# STM32H7.net
KiCad netlist of a schematic drawn in Altium Designer
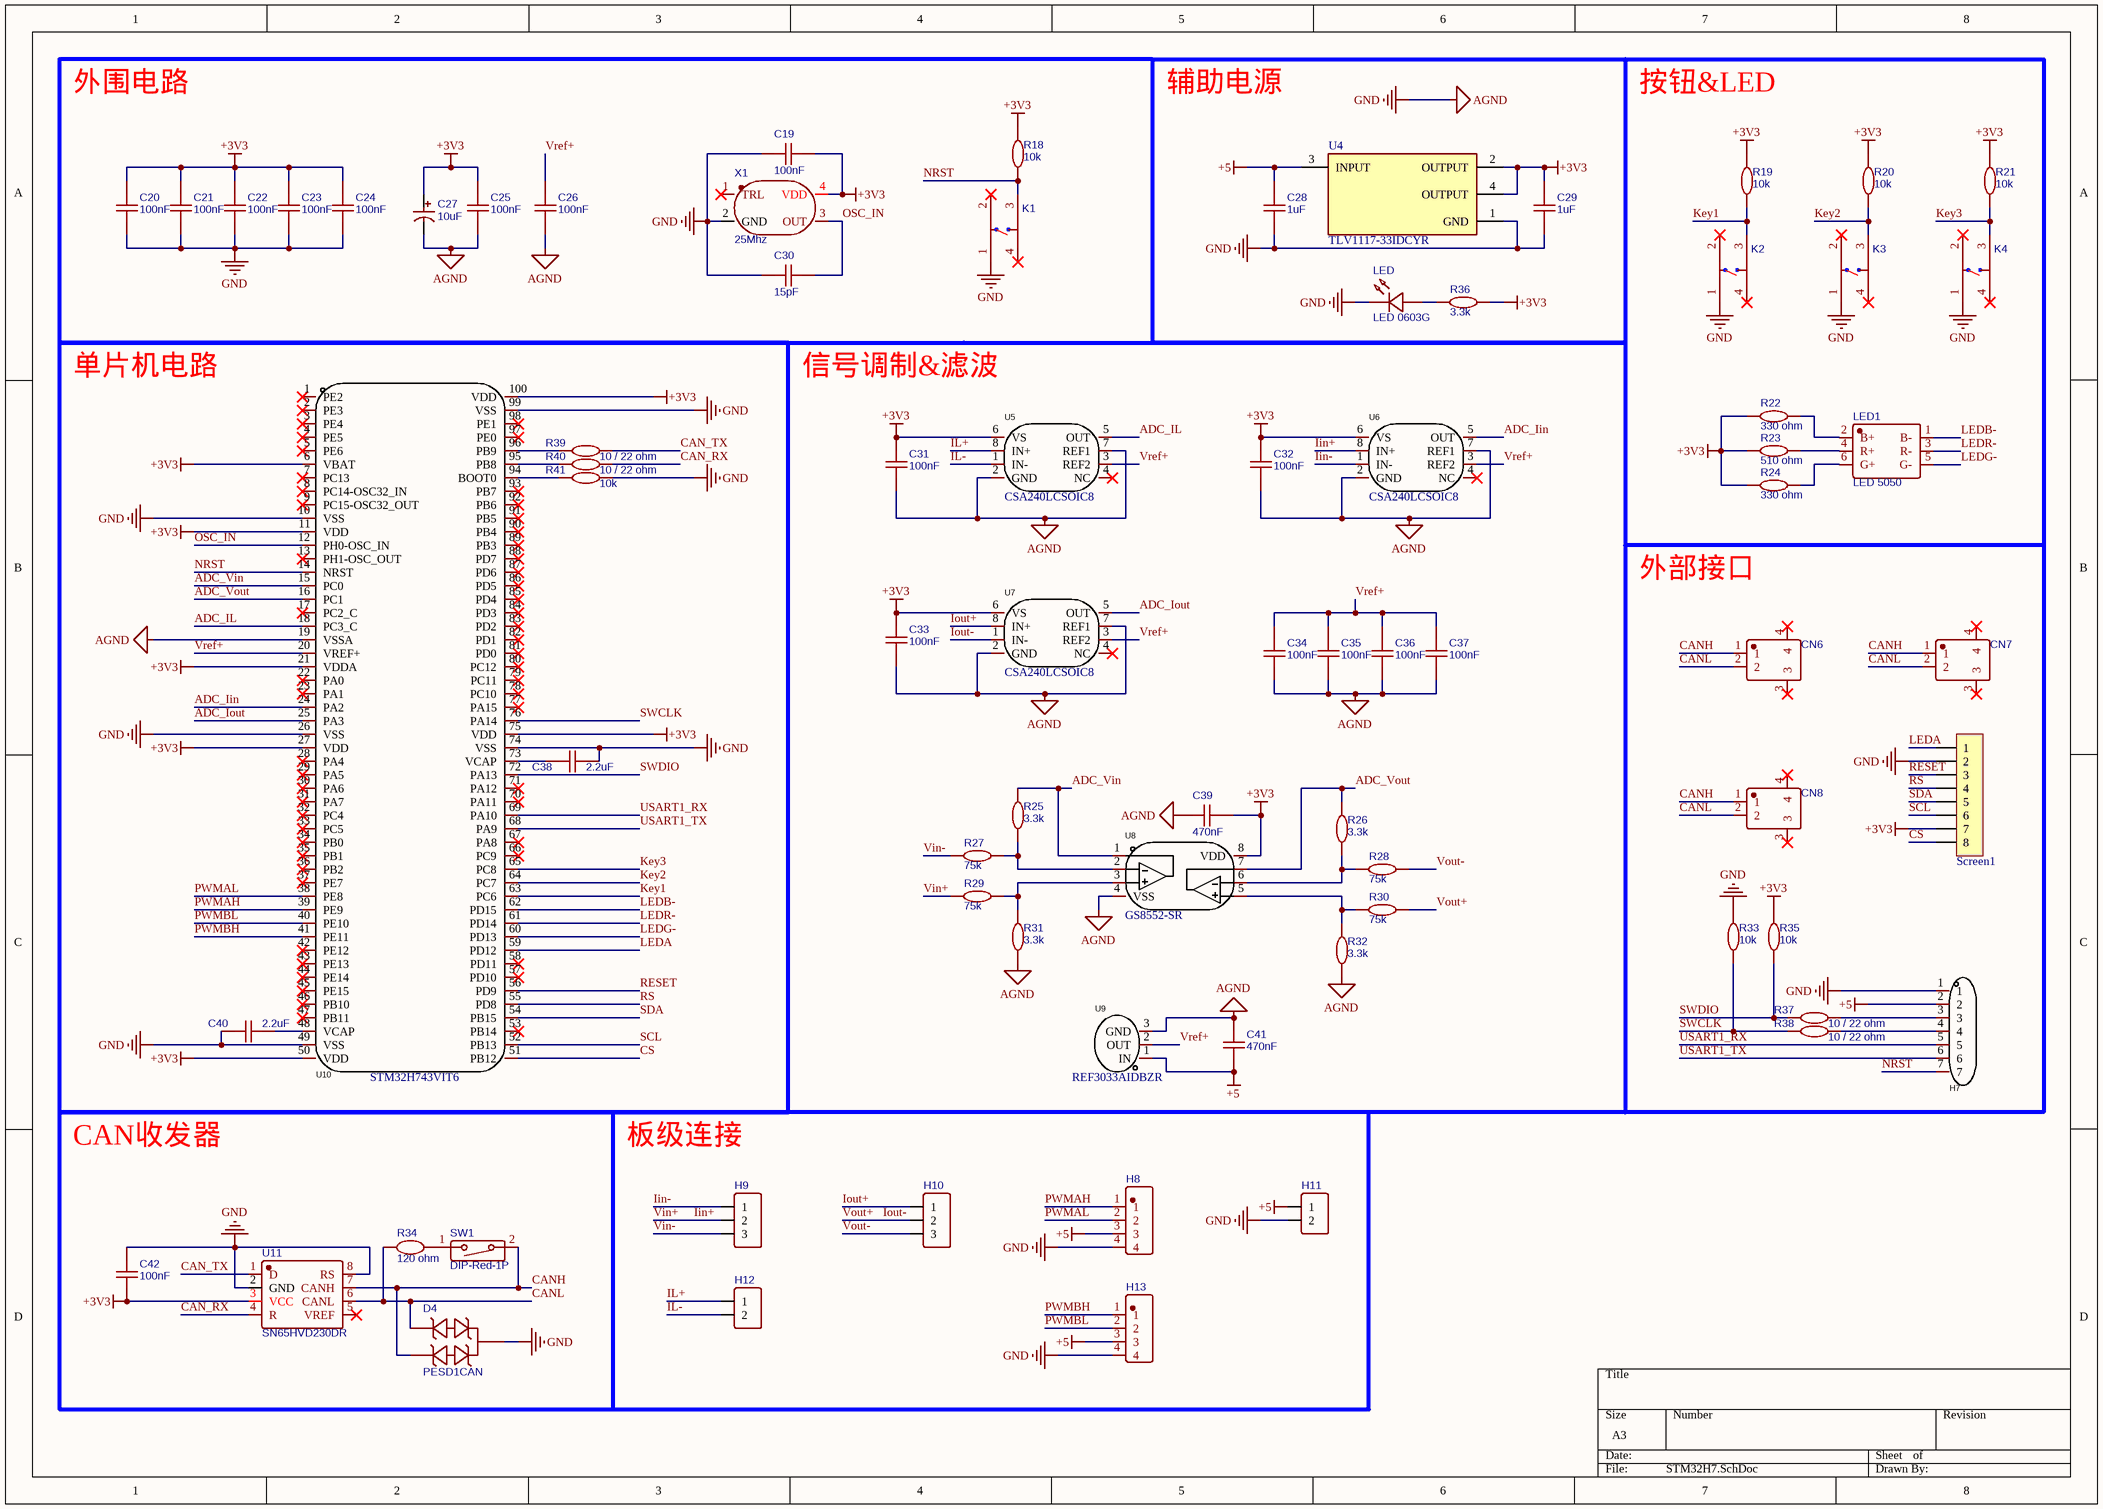
[diagram p0: STM32H7.SchDoc]

(export (version "E")
  (design (tool "Eeschema 10.0.6"))
  (components
    (comp (ref "C19")
      (value "100nF")
      (footprint "C0603")
      (fields
        (field (name "BOM_MANUFACTURER PART") "CC0603KRX7R9BB104")
        (field (name "BOM_SUPPLIER PART") "C14663")
      )
      (libsource (lib "RC_schlib") (part "C0603"))
    )
    (comp (ref "C20")
      (value "100nF")
      (footprint "C0603")
      (fields
        (field (name "BOM_MANUFACTURER PART") "CC0603KRX7R9BB104")
        (field (name "BOM_SUPPLIER PART") "C14663")
      )
      (libsource (lib "RC_schlib") (part "C0603"))
    )
    (comp (ref "C21")
      (value "100nF")
      (footprint "C0603")
      (fields
        (field (name "BOM_MANUFACTURER PART") "CC0603KRX7R9BB104")
        (field (name "BOM_SUPPLIER PART") "C14663")
      )
      (libsource (lib "RC_schlib") (part "C0603"))
    )
    (comp (ref "C22")
      (value "100nF")
      (footprint "C0603")
      (fields
        (field (name "BOM_MANUFACTURER PART") "CC0603KRX7R9BB104")
        (field (name "BOM_SUPPLIER PART") "C14663")
      )
      (libsource (lib "RC_schlib") (part "C0603"))
    )
    (comp (ref "C23")
      (value "100nF")
      (footprint "C0603")
      (fields
        (field (name "BOM_MANUFACTURER PART") "CC0603KRX7R9BB104")
        (field (name "BOM_SUPPLIER PART") "C14663")
      )
      (libsource (lib "RC_schlib") (part "C0603"))
    )
    (comp (ref "C24")
      (value "100nF")
      (footprint "C0603")
      (fields
        (field (name "BOM_MANUFACTURER PART") "CC0603KRX7R9BB104")
        (field (name "BOM_SUPPLIER PART") "C14663")
      )
      (libsource (lib "RC_schlib") (part "C0603"))
    )
    (comp (ref "C25")
      (value "100nF")
      (footprint "C0603")
      (fields
        (field (name "BOM_MANUFACTURER PART") "CC0603KRX7R9BB104")
        (field (name "BOM_SUPPLIER PART") "C14663")
      )
      (libsource (lib "RC_schlib") (part "C0603"))
    )
    (comp (ref "C26")
      (value "100nF")
      (footprint "C0603")
      (fields
        (field (name "BOM_MANUFACTURER PART") "CC0603KRX7R9BB104")
        (field (name "BOM_SUPPLIER PART") "C14663")
      )
      (libsource (lib "RC_schlib") (part "C0603"))
    )
    (comp (ref "C27")
      (value "10uF")
      (footprint "CD A(3216)")
      (description "长3.2mm，宽1.6mm，厚1.6mm")
      (fields
        (field (name "BOM_MANUFACTURER PART") "50V 100uF 8X12")
        (field (name "BOM_SUPPLIER PART") "C2749")
      )
      (libsource (lib "eCap_schlib") (part "A型钽电容"))
    )
    (comp (ref "C28")
      (value "1uF")
      (footprint "C0603")
      (fields
        (field (name "BOM_MANUFACTURER PART") "CC0603KRX7R9BB104")
        (field (name "BOM_SUPPLIER PART") "C14663")
      )
      (libsource (lib "RC_schlib") (part "C0603"))
    )
    (comp (ref "C29")
      (value "1uF")
      (footprint "C0603")
      (fields
        (field (name "BOM_MANUFACTURER PART") "CC0603KRX7R9BB104")
        (field (name "BOM_SUPPLIER PART") "C14663")
      )
      (libsource (lib "RC_schlib") (part "C0603"))
    )
    (comp (ref "C30")
      (value "15pF")
      (footprint "C0603")
      (fields
        (field (name "BOM_MANUFACTURER PART") "CC0603KRX7R9BB104")
        (field (name "BOM_SUPPLIER PART") "C14663")
      )
      (libsource (lib "RC_schlib") (part "C0603"))
    )
    (comp (ref "C31")
      (value "100nF")
      (footprint "C0603")
      (fields
        (field (name "BOM_MANUFACTURER PART") "CC0603KRX7R9BB104")
        (field (name "BOM_SUPPLIER PART") "C14663")
      )
      (libsource (lib "RC_schlib") (part "C0603"))
    )
    (comp (ref "C32")
      (value "100nF")
      (footprint "C0603")
      (fields
        (field (name "BOM_MANUFACTURER PART") "CC0603KRX7R9BB104")
        (field (name "BOM_SUPPLIER PART") "C14663")
      )
      (libsource (lib "RC_schlib") (part "C0603"))
    )
    (comp (ref "C33")
      (value "100nF")
      (footprint "C0603")
      (fields
        (field (name "BOM_MANUFACTURER PART") "CC0603KRX7R9BB104")
        (field (name "BOM_SUPPLIER PART") "C14663")
      )
      (libsource (lib "RC_schlib") (part "C0603"))
    )
    (comp (ref "C34")
      (value "100nF")
      (footprint "C0603")
      (fields
        (field (name "BOM_MANUFACTURER PART") "CC0603KRX7R9BB104")
        (field (name "BOM_SUPPLIER PART") "C14663")
      )
      (libsource (lib "RC_schlib") (part "C0603"))
    )
    (comp (ref "C35")
      (value "100nF")
      (footprint "C0603")
      (fields
        (field (name "BOM_MANUFACTURER PART") "CC0603KRX7R9BB104")
        (field (name "BOM_SUPPLIER PART") "C14663")
      )
      (libsource (lib "RC_schlib") (part "C0603"))
    )
    (comp (ref "C36")
      (value "100nF")
      (footprint "C0603")
      (fields
        (field (name "BOM_MANUFACTURER PART") "CC0603KRX7R9BB104")
        (field (name "BOM_SUPPLIER PART") "C14663")
      )
      (libsource (lib "RC_schlib") (part "C0603"))
    )
    (comp (ref "C37")
      (value "100nF")
      (footprint "C0603")
      (fields
        (field (name "BOM_MANUFACTURER PART") "CC0603KRX7R9BB104")
        (field (name "BOM_SUPPLIER PART") "C14663")
      )
      (libsource (lib "RC_schlib") (part "C0603"))
    )
    (comp (ref "C38")
      (value "2.2uF")
      (footprint "C0603")
      (fields
        (field (name "BOM_MANUFACTURER PART") "CC0603KRX7R9BB104")
        (field (name "BOM_SUPPLIER PART") "C14663")
      )
      (libsource (lib "RC_schlib") (part "C0603"))
    )
    (comp (ref "C39")
      (value "470nF")
      (footprint "C0603")
      (fields
        (field (name "BOM_MANUFACTURER PART") "CC0603KRX7R9BB104")
        (field (name "BOM_SUPPLIER PART") "C14663")
      )
      (libsource (lib "RC_schlib") (part "C0603"))
    )
    (comp (ref "C40")
      (value "2.2uF")
      (footprint "C0603")
      (fields
        (field (name "BOM_MANUFACTURER PART") "CC0603KRX7R9BB104")
        (field (name "BOM_SUPPLIER PART") "C14663")
      )
      (libsource (lib "RC_schlib") (part "C0603"))
    )
    (comp (ref "C41")
      (value "470nF")
      (footprint "C0603")
      (fields
        (field (name "BOM_MANUFACTURER PART") "CC0603KRX7R9BB104")
        (field (name "BOM_SUPPLIER PART") "C14663")
      )
      (libsource (lib "RC_schlib") (part "C0603"))
    )
    (comp (ref "C42")
      (value "100nF")
      (footprint "C0603")
      (fields
        (field (name "BOM_MANUFACTURER PART") "CC0603KRX7R9BB104")
        (field (name "BOM_SUPPLIER PART") "C14663")
      )
      (libsource (lib "RC_schlib") (part "C0603"))
    )
    (comp (ref "CN6")
      (value "A1257WR-S-2P")
      (footprint "CONN-SMD_A1257WR-S-2P")
      (fields
        (field (name "BOM_SUPPLIER PART") "C225118")
        (field (name "BOM_MANUFACTURER PART") "A1257WV-S-2P")
      )
      (libsource (lib "GH1.25_schlib") (part "A1257WR-S-2P"))
    )
    (comp (ref "CN7")
      (value "A1257WR-S-2P")
      (footprint "CONN-SMD_A1257WR-S-2P")
      (fields
        (field (name "BOM_SUPPLIER PART") "C225118")
        (field (name "BOM_MANUFACTURER PART") "A1257WV-S-2P")
      )
      (libsource (lib "GH1.25_schlib") (part "A1257WR-S-2P"))
    )
    (comp (ref "CN8")
      (value "A1257WR-S-2P")
      (footprint "CONN-SMD_A1257WR-S-2P")
      (fields
        (field (name "BOM_SUPPLIER PART") "C225118")
        (field (name "BOM_MANUFACTURER PART") "A1257WV-S-2P")
      )
      (libsource (lib "GH1.25_schlib") (part "A1257WR-S-2P"))
    )
    (comp (ref "D4")
      (value "PESD1CAN")
      (footprint "SOT-23-3_L2.9-W1.6-P1.90-LS2.8-BR")
      (fields (field (name "BOM_SUPPLIER PART") "C907838"))
      (libsource (lib "MB") (part "PESD1CAN"))
    )
    (comp (ref "H7")
      (value "7P卧贴排母")
      (footprint "HDR-SMD_7P-P2.54-H-F-L11.5")
      (fields
        (field (name "MANUFACTURER") "XKB Connectivity(中国星坤)")
        (field (name "MANUFACTURER PART") "X6511FRS-07-C85D30")
      )
      (libsource (lib "2.54CN_schlib") (part "7P卧贴排母"))
    )
    (comp (ref "H8")
      (value "Header-Female-2.54_1x4")
      (footprint "HDR2.54-M-LI-4P")
      (fields (field (name "BOM_SUPPLIER PART") "C247921"))
      (libsource (lib "2.54CN_schlib") (part "Header-Female-2.54_1x4"))
    )
    (comp (ref "H9")
      (value "Header-Female-2.54_1x3")
      (footprint "HDR2.54-M-LI-3P")
      (fields
        (field (name "BOM_MANUFACTURER PART") "Header2.54mm 1*3P")
        (field (name "BOM_SUPPLIER PART") "C49257")
      )
      (libsource (lib "2.54CN_schlib") (part "Header-Female-2.54_1x3"))
    )
    (comp (ref "H10")
      (value "Header-Female-2.54_1x3")
      (footprint "HDR2.54-M-LI-3P")
      (fields
        (field (name "BOM_MANUFACTURER PART") "Header2.54mm 1*3P")
        (field (name "BOM_SUPPLIER PART") "C49257")
      )
      (libsource (lib "2.54CN_schlib") (part "Header-Female-2.54_1x3"))
    )
    (comp (ref "H11")
      (value "Header-Female-2.54_1x2")
      (footprint "HDR2.54-M-LI-2P")
      (fields
        (field (name "BOM_MANUFACTURER PART") "Header2.54mm 1*3P")
        (field (name "BOM_SUPPLIER PART") "C49257")
      )
      (libsource (lib "2.54CN_schlib") (part "Header-Female-2.54_1x2"))
    )
    (comp (ref "H12")
      (value "Header-Female-2.54_1x2")
      (footprint "HDR2.54-M-LI-2P")
      (fields
        (field (name "BOM_MANUFACTURER PART") "Header2.54mm 1*3P")
        (field (name "BOM_SUPPLIER PART") "C49257")
      )
      (libsource (lib "2.54CN_schlib") (part "Header-Female-2.54_1x2"))
    )
    (comp (ref "H13")
      (value "Header-Female-2.54_1x4")
      (footprint "HDR2.54-M-LI-4P")
      (fields (field (name "BOM_SUPPLIER PART") "C247921"))
      (libsource (lib "2.54CN_schlib") (part "Header-Female-2.54_1x4"))
    )
    (comp (ref "K1")
      (value "TSW SMD-6*6*5")
      (footprint "TSW SMD-6*6*5")
      (fields
        (field (name "BOM_SUPPLIER PART") "C231715")
        (field (name "BOM_MANUFACTURER PART") "KAN0661-1001B")
      )
      (libsource (lib "Button_schlib") (part "TSW SMD-6*6*5"))
    )
    (comp (ref "K2")
      (value "TSW SMD-6*6*5")
      (footprint "TSW SMD-6*6*5")
      (fields
        (field (name "BOM_SUPPLIER PART") "C231715")
        (field (name "BOM_MANUFACTURER PART") "KAN0661-1001B")
      )
      (libsource (lib "Button_schlib") (part "TSW SMD-6*6*5"))
    )
    (comp (ref "K3")
      (value "TSW SMD-6*6*5")
      (footprint "TSW SMD-6*6*5")
      (fields
        (field (name "BOM_SUPPLIER PART") "C231715")
        (field (name "BOM_MANUFACTURER PART") "KAN0661-1001B")
      )
      (libsource (lib "Button_schlib") (part "TSW SMD-6*6*5"))
    )
    (comp (ref "K4")
      (value "TSW SMD-6*6*5")
      (footprint "TSW SMD-6*6*5")
      (fields
        (field (name "BOM_SUPPLIER PART") "C231715")
        (field (name "BOM_MANUFACTURER PART") "KAN0661-1001B")
      )
      (libsource (lib "Button_schlib") (part "TSW SMD-6*6*5"))
    )
    (comp (ref "LED")
      (value "LED 0603G")
      (footprint "LED 0603G")
      (description "绿色0603LED")
      (fields
        (field (name "BOM_SUPPLIER PART") "C3014404")
        (field (name "BOM_MANUFACTURER PART") "11-21/BHC-AQ2S2/2T")
      )
      (libsource (lib "LED_schlib") (part "LED 0603G"))
    )
    (comp (ref "LED1")
      (value "LED 5050")
      (footprint "LED 5050")
      (description "5050RGB-LED")
      (fields
        (field (name "BOM_SUPPLIER PART") "C3014404")
        (field (name "BOM_MANUFACTURER PART") "11-21/BHC-AQ2S2/2T")
      )
      (libsource (lib "LED_schlib") (part "LED 5050"))
    )
    (comp (ref "R18")
      (value "10k")
      (footprint "R0603")
      (fields
        (field (name "BOM_SUPPLIER PART") "C326890")
        (field (name "BOM_MANUFACTURER PART") "SR0603JR-071RL")
      )
      (libsource (lib "RC_schlib") (part "R0603"))
    )
    (comp (ref "R19")
      (value "10k")
      (footprint "R0603")
      (fields
        (field (name "BOM_SUPPLIER PART") "C326890")
        (field (name "BOM_MANUFACTURER PART") "SR0603JR-071RL")
      )
      (libsource (lib "RC_schlib") (part "R0603"))
    )
    (comp (ref "R20")
      (value "10k")
      (footprint "R0603")
      (fields
        (field (name "BOM_SUPPLIER PART") "C326890")
        (field (name "BOM_MANUFACTURER PART") "SR0603JR-071RL")
      )
      (libsource (lib "RC_schlib") (part "R0603"))
    )
    (comp (ref "R21")
      (value "10k")
      (footprint "R0603")
      (fields
        (field (name "BOM_SUPPLIER PART") "C326890")
        (field (name "BOM_MANUFACTURER PART") "SR0603JR-071RL")
      )
      (libsource (lib "RC_schlib") (part "R0603"))
    )
    (comp (ref "R22")
      (value "330 ohm")
      (footprint "R0603")
      (fields
        (field (name "BOM_SUPPLIER PART") "C326890")
        (field (name "BOM_MANUFACTURER PART") "SR0603JR-071RL")
      )
      (libsource (lib "RC_schlib") (part "R0603"))
    )
    (comp (ref "R23")
      (value "510 ohm")
      (footprint "R0603")
      (fields
        (field (name "BOM_SUPPLIER PART") "C326890")
        (field (name "BOM_MANUFACTURER PART") "SR0603JR-071RL")
      )
      (libsource (lib "RC_schlib") (part "R0603"))
    )
    (comp (ref "R24")
      (value "330 ohm")
      (footprint "R0603")
      (fields
        (field (name "BOM_SUPPLIER PART") "C326890")
        (field (name "BOM_MANUFACTURER PART") "SR0603JR-071RL")
      )
      (libsource (lib "RC_schlib") (part "R0603"))
    )
    (comp (ref "R25")
      (value "3.3k")
      (footprint "R0603")
      (fields
        (field (name "BOM_SUPPLIER PART") "C326890")
        (field (name "BOM_MANUFACTURER PART") "SR0603JR-071RL")
      )
      (libsource (lib "RC_schlib") (part "R0603"))
    )
    (comp (ref "R26")
      (value "3.3k")
      (footprint "R0603")
      (fields
        (field (name "BOM_SUPPLIER PART") "C326890")
        (field (name "BOM_MANUFACTURER PART") "SR0603JR-071RL")
      )
      (libsource (lib "RC_schlib") (part "R0603"))
    )
    (comp (ref "R27")
      (value "75k")
      (footprint "R0603")
      (fields
        (field (name "BOM_SUPPLIER PART") "C326890")
        (field (name "BOM_MANUFACTURER PART") "SR0603JR-071RL")
      )
      (libsource (lib "RC_schlib") (part "R0603"))
    )
    (comp (ref "R28")
      (value "75k")
      (footprint "R0603")
      (fields
        (field (name "BOM_SUPPLIER PART") "C326890")
        (field (name "BOM_MANUFACTURER PART") "SR0603JR-071RL")
      )
      (libsource (lib "RC_schlib") (part "R0603"))
    )
    (comp (ref "R29")
      (value "75k")
      (footprint "R0603")
      (fields
        (field (name "BOM_SUPPLIER PART") "C326890")
        (field (name "BOM_MANUFACTURER PART") "SR0603JR-071RL")
      )
      (libsource (lib "RC_schlib") (part "R0603"))
    )
    (comp (ref "R30")
      (value "75k")
      (footprint "R0603")
      (fields
        (field (name "BOM_SUPPLIER PART") "C326890")
        (field (name "BOM_MANUFACTURER PART") "SR0603JR-071RL")
      )
      (libsource (lib "RC_schlib") (part "R0603"))
    )
    (comp (ref "R31")
      (value "3.3k")
      (footprint "R0603")
      (fields
        (field (name "BOM_SUPPLIER PART") "C326890")
        (field (name "BOM_MANUFACTURER PART") "SR0603JR-071RL")
      )
      (libsource (lib "RC_schlib") (part "R0603"))
    )
    (comp (ref "R32")
      (value "3.3k")
      (footprint "R0603")
      (fields
        (field (name "BOM_SUPPLIER PART") "C326890")
        (field (name "BOM_MANUFACTURER PART") "SR0603JR-071RL")
      )
      (libsource (lib "RC_schlib") (part "R0603"))
    )
    (comp (ref "R33")
      (value "10k")
      (footprint "R0603")
      (fields
        (field (name "BOM_SUPPLIER PART") "C326890")
        (field (name "BOM_MANUFACTURER PART") "SR0603JR-071RL")
      )
      (libsource (lib "RC_schlib") (part "R0603"))
    )
    (comp (ref "R34")
      (value "120 ohm")
      (footprint "R0805")
      (fields
        (field (name "BOM_SUPPLIER PART") "C723409")
        (field (name "BOM_MANUFACTURER PART") "SR0805FR-0710RL")
      )
      (libsource (lib "RC_schlib") (part "R0805"))
    )
    (comp (ref "R35")
      (value "10k")
      (footprint "R0603")
      (fields
        (field (name "BOM_SUPPLIER PART") "C326890")
        (field (name "BOM_MANUFACTURER PART") "SR0603JR-071RL")
      )
      (libsource (lib "RC_schlib") (part "R0603"))
    )
    (comp (ref "R36")
      (value "3.3k")
      (footprint "R0603")
      (fields
        (field (name "BOM_SUPPLIER PART") "C326890")
        (field (name "BOM_MANUFACTURER PART") "SR0603JR-071RL")
      )
      (libsource (lib "RC_schlib") (part "R0603"))
    )
    (comp (ref "R37")
      (value "10 / 22 ohm")
      (footprint "R0603")
      (fields
        (field (name "BOM_SUPPLIER PART") "C326890")
        (field (name "BOM_MANUFACTURER PART") "SR0603JR-071RL")
      )
      (libsource (lib "RC_schlib") (part "R0603"))
    )
    (comp (ref "R38")
      (value "10 / 22 ohm")
      (footprint "R0603")
      (fields
        (field (name "BOM_SUPPLIER PART") "C326890")
        (field (name "BOM_MANUFACTURER PART") "SR0603JR-071RL")
      )
      (libsource (lib "RC_schlib") (part "R0603"))
    )
    (comp (ref "R39")
      (value "10 / 22 ohm")
      (footprint "R0603")
      (fields
        (field (name "BOM_SUPPLIER PART") "C326890")
        (field (name "BOM_MANUFACTURER PART") "SR0603JR-071RL")
      )
      (libsource (lib "RC_schlib") (part "R0603"))
    )
    (comp (ref "R40")
      (value "10 / 22 ohm")
      (footprint "R0603")
      (fields
        (field (name "BOM_SUPPLIER PART") "C326890")
        (field (name "BOM_MANUFACTURER PART") "SR0603JR-071RL")
      )
      (libsource (lib "RC_schlib") (part "R0603"))
    )
    (comp (ref "R41")
      (value "10k")
      (footprint "R0603")
      (fields
        (field (name "BOM_SUPPLIER PART") "C326890")
        (field (name "BOM_MANUFACTURER PART") "SR0603JR-071RL")
      )
      (libsource (lib "RC_schlib") (part "R0603"))
    )
    (comp (ref "Screen1")
      (value "FPC1.0-8P")
      (footprint "FPC0.5 2H-S-W-8P")
      (description "FPC连接器")
      (libsource (lib "FPC_schlib") (part "FPC-8P-0.5"))
    )
    (comp (ref "SW1")
      (value "DIP-Red-1P")
      (footprint "CSW DIP-1P_G")
      (fields (field (name "BOM_SUPPLIER PART") "C45226") (field (name "BOM_MANUFACTURER PART") "VDG-10HG-R"))
      (libsource (lib "Dip-Switch_schlib") (part "DIP-Red-1P"))
    )
    (comp (ref "U4")
      (value "TLV1117-33IDCYR")
      (footprint "FP-DCY0004A-MFG")
      (description "IC REG LIN 3.3V 800MA SOT223-4")
      (fields
        (field (name "MANUFACTURER") "Texas Instruments")
        (field (name "OCTOPART") "https://octopart.com/tlv1117-33idcyr-texas+instruments-669250")
      )
      (libsource (lib "Altium Content Vault") (part "d420fb9686013fb832e66295cdf4acf"))
    )
    (comp (ref "U5")
      (value "CSA240LCSOIC8")
      (footprint "SOIC-8_L4.9-W3.9-P1.27-LS6.0-BL")
      (description "低噪声低温漂双向电流高端检测芯片")
      (fields (field (name "MANUFACTURER") "analogysemi(类比半导体)"))
      (libsource (lib "IC_schlib") (part "CSA240LCSOIC8"))
    )
    (comp (ref "U6")
      (value "CSA240LCSOIC8")
      (footprint "SOIC-8_L4.9-W3.9-P1.27-LS6.0-BL")
      (description "低噪声低温漂双向电流高端检测芯片")
      (fields (field (name "MANUFACTURER") "analogysemi(类比半导体)"))
      (libsource (lib "IC_schlib") (part "CSA240LCSOIC8"))
    )
    (comp (ref "U7")
      (value "CSA240LCSOIC8")
      (footprint "SOIC-8_L4.9-W3.9-P1.27-LS6.0-BL")
      (description "低噪声低温漂双向电流高端检测芯片")
      (fields (field (name "MANUFACTURER") "analogysemi(类比半导体)"))
      (libsource (lib "IC_schlib") (part "CSA240LCSOIC8"))
    )
    (comp (ref "U8")
      (value "GS8552-SR")
      (footprint "SOIC-8_L4.9-W3.9-P1.27-LS6.0-BL")
      (description "1.5MHZ, 轨到轨高精双通道运放")
      (fields (field (name "MANUFACTURER") "Gainsil(聚洵)"))
      (libsource (lib "IC_schlib") (part "GS8552-SR"))
    )
    (comp (ref "U9")
      (value "REF3033AIDBZR")
      (footprint "SOT-23-3_L3.0-W1.7-P0.95-LS2.9-BR")
      (description "3.3V基准电压源")
      (fields (field (name "MANUFACTURER") "TI(德州仪器)") (field (name "TOLERANCE") "±0.2%"))
      (libsource (lib "IC_schlib") (part "REF3033AIDBZR"))
    )
    (comp (ref "U10")
      (value "STM32H743VIT6")
      (footprint "LQFP-100_L14.0-W14.0-P0.50-LS16.0-BL")
      (description "STM32H7")
      (fields (field (name "MANUFACTURER") "ST(意法半导体)"))
      (libsource (lib "IC_schlib") (part "STM32H743VIT6"))
    )
    (comp (ref "U11")
      (value "SN65HVD230DR")
      (footprint "SOP-8")
      (description "常用CAN收发器")
      (fields (field (name "BOM_SUPPLIER PART") "C12084"))
      (libsource (lib "IC_schlib") (part "SN65HVD230DR"))
    )
    (comp (ref "X1")
      (value "25Mhz")
      (footprint "OSC 3225-4P")
      (fields
        (field (name "BOM_SUPPLIER PART") "C454610")
        (field (name "BOM_MANUFACTURER PART") "TFOM8M4RHKCNT2T")
      )
      (libsource (lib "OSC_schilb") (part "OSC-3225"))
    )
  )
  (nets
    (net (code "1") (name "+3V3") (class "Default")
      (node (ref "C19") (pin "2") (pinfunction "2_2") (pintype "passive"))
      (node (ref "C20") (pin "2") (pinfunction "2_2") (pintype "passive"))
      (node (ref "C21") (pin "2") (pinfunction "2_2") (pintype "passive"))
      (node (ref "C22") (pin "2") (pinfunction "2_2") (pintype "passive"))
      (node (ref "C23") (pin "2") (pinfunction "2_2") (pintype "passive"))
      (node (ref "C24") (pin "2") (pinfunction "2_2") (pintype "passive"))
      (node (ref "C25") (pin "1") (pinfunction "1_1") (pintype "passive"))
      (node (ref "C27") (pin "1") (pinfunction "1_1") (pintype "passive"))
      (node (ref "C29") (pin "2") (pinfunction "2_2") (pintype "passive"))
      (node (ref "C31") (pin "2") (pinfunction "2_2") (pintype "passive"))
      (node (ref "C32") (pin "2") (pinfunction "2_2") (pintype "passive"))
      (node (ref "C33") (pin "2") (pinfunction "2_2") (pintype "passive"))
      (node (ref "C39") (pin "2") (pinfunction "2_2") (pintype "passive"))
      (node (ref "C42") (pin "1") (pinfunction "1_1") (pintype "passive"))
      (node (ref "R18") (pin "2") (pinfunction "2_2") (pintype "passive"))
      (node (ref "R19") (pin "2") (pinfunction "2_2") (pintype "passive"))
      (node (ref "R20") (pin "2") (pinfunction "2_2") (pintype "passive"))
      (node (ref "R21") (pin "2") (pinfunction "2_2") (pintype "passive"))
      (node (ref "R22") (pin "2") (pinfunction "2_2") (pintype "passive"))
      (node (ref "R23") (pin "2") (pinfunction "2_2") (pintype "passive"))
      (node (ref "R24") (pin "2") (pinfunction "2_2") (pintype "passive"))
      (node (ref "R35") (pin "2") (pinfunction "2_2") (pintype "passive"))
      (node (ref "R36") (pin "1") (pinfunction "1_1") (pintype "passive"))
      (node (ref "Screen1") (pin "7") (pinfunction "7_7") (pintype "passive"))
      (node (ref "U10") (pin "100") (pinfunction "VDD_100") (pintype "passive"))
      (node (ref "U10") (pin "11") (pinfunction "VDD_11") (pintype "passive"))
      (node (ref "U10") (pin "21") (pinfunction "VDDA_21") (pintype "passive"))
      (node (ref "U10") (pin "27") (pinfunction "VDD_27") (pintype "passive"))
      (node (ref "U10") (pin "50") (pinfunction "VDD_50") (pintype "passive"))
      (node (ref "U10") (pin "6") (pinfunction "VBAT_6") (pintype "passive"))
      (node (ref "U10") (pin "75") (pinfunction "VDD_75") (pintype "passive"))
      (node (ref "U11") (pin "3") (pinfunction "VCC_3") (pintype "passive"))
      (node (ref "U4") (pin "2") (pinfunction "OUTPUT_2") (pintype "power_in"))
      (node (ref "U4") (pin "4") (pinfunction "OUTPUT_4") (pintype "power_in"))
      (node (ref "U5") (pin "6") (pinfunction "VS_6") (pintype "passive"))
      (node (ref "U6") (pin "6") (pinfunction "VS_6") (pintype "passive"))
      (node (ref "U7") (pin "6") (pinfunction "VS_6") (pintype "passive"))
      (node (ref "U8") (pin "8") (pinfunction "VDD_8") (pintype "passive"))
      (node (ref "X1") (pin "4") (pinfunction "VDD_4") (pintype "passive"))
    )
    (net (code "2") (name "+5") (class "Default")
      (node (ref "C28") (pin "2") (pinfunction "2_2") (pintype "passive"))
      (node (ref "C41") (pin "1") (pinfunction "1_1") (pintype "passive"))
      (node (ref "H11") (pin "1") (pinfunction "1_1") (pintype "passive"))
      (node (ref "H13") (pin "3") (pinfunction "3_3") (pintype "passive"))
      (node (ref "H7") (pin "2") (pinfunction "2_2") (pintype "passive"))
      (node (ref "H8") (pin "3") (pinfunction "3_3") (pintype "passive"))
      (node (ref "U4") (pin "3") (pinfunction "INPUT_3") (pintype "power_in"))
      (node (ref "U9") (pin "1") (pinfunction "IN_1") (pintype "passive"))
    )
    (net (code "3") (name "/ADC_IL") (class "Default")
      (node (ref "U10") (pin "18") (pinfunction "PC3_C_18") (pintype "passive"))
      (node (ref "U5") (pin "5") (pinfunction "OUT_5") (pintype "passive"))
    )
    (net (code "4") (name "/ADC_Iin") (class "Default")
      (node (ref "U10") (pin "24") (pinfunction "PA2_24") (pintype "passive"))
      (node (ref "U6") (pin "5") (pinfunction "OUT_5") (pintype "passive"))
    )
    (net (code "5") (name "/ADC_Iout") (class "Default")
      (node (ref "U10") (pin "25") (pinfunction "PA3_25") (pintype "passive"))
      (node (ref "U7") (pin "5") (pinfunction "OUT_5") (pintype "passive"))
    )
    (net (code "6") (name "/ADC_Vin") (class "Default")
      (node (ref "R25") (pin "2") (pinfunction "2_2") (pintype "passive"))
      (node (ref "U10") (pin "15") (pinfunction "PC0_15") (pintype "passive"))
      (node (ref "U8") (pin "1") (pinfunction "OUTA_1") (pintype "passive"))
    )
    (net (code "7") (name "/ADC_Vout") (class "Default")
      (node (ref "R26") (pin "2") (pinfunction "2_2") (pintype "passive"))
      (node (ref "U10") (pin "16") (pinfunction "PC1_16") (pintype "passive"))
      (node (ref "U8") (pin "7") (pinfunction "OUTB_7") (pintype "passive"))
    )
    (net (code "8") (name "/CANH") (class "Default")
      (node (ref "CN6") (pin "1") (pinfunction "1_1") (pintype "passive"))
      (node (ref "CN7") (pin "1") (pinfunction "1_1") (pintype "passive"))
      (node (ref "CN8") (pin "1") (pinfunction "1_1") (pintype "passive"))
      (node (ref "D4") (pin "2") (pinfunction "2_2") (pintype "passive"))
      (node (ref "SW1") (pin "2") (pinfunction "2_2") (pintype "passive"))
      (node (ref "U11") (pin "7") (pinfunction "CANH_7") (pintype "passive"))
    )
    (net (code "9") (name "/CANL") (class "Default")
      (node (ref "CN6") (pin "2") (pinfunction "2_2") (pintype "passive"))
      (node (ref "CN7") (pin "2") (pinfunction "2_2") (pintype "passive"))
      (node (ref "CN8") (pin "2") (pinfunction "2_2") (pintype "passive"))
      (node (ref "D4") (pin "1") (pinfunction "1_1") (pintype "passive"))
      (node (ref "R34") (pin "1") (pinfunction "1_1") (pintype "passive"))
      (node (ref "U11") (pin "6") (pinfunction "CANL_6") (pintype "passive"))
    )
    (net (code "10") (name "/CAN_RX") (class "Default")
      (node (ref "R40") (pin "1") (pinfunction "1_1") (pintype "passive"))
      (node (ref "U11") (pin "4") (pinfunction "R_4") (pintype "passive"))
    )
    (net (code "11") (name "/CAN_TX") (class "Default")
      (node (ref "R39") (pin "1") (pinfunction "1_1") (pintype "passive"))
      (node (ref "U11") (pin "1") (pinfunction "D_1") (pintype "passive"))
    )
    (net (code "12") (name "/CS") (class "Default")
      (node (ref "Screen1") (pin "8") (pinfunction "8_8") (pintype "passive"))
      (node (ref "U10") (pin "51") (pinfunction "PB12_51") (pintype "passive"))
    )
    (net (code "13") (name "/IL+") (class "Default")
      (node (ref "H12") (pin "1") (pinfunction "1_1") (pintype "passive"))
      (node (ref "U5") (pin "8") (pinfunction "IN+_8") (pintype "passive"))
    )
    (net (code "14") (name "/IL-") (class "Default")
      (node (ref "H12") (pin "2") (pinfunction "2_2") (pintype "passive"))
      (node (ref "U5") (pin "1") (pinfunction "IN-_1") (pintype "passive"))
    )
    (net (code "15") (name "/Iin+") (class "Default")
      (node (ref "H9") (pin "2") (pinfunction "2_2") (pintype "passive"))
      (node (ref "R29") (pin "1") (pinfunction "1_1") (pintype "passive"))
      (node (ref "U6") (pin "8") (pinfunction "IN+_8") (pintype "passive"))
    )
    (net (code "16") (name "/Iin-") (class "Default")
      (node (ref "H9") (pin "1") (pinfunction "1_1") (pintype "passive"))
      (node (ref "U6") (pin "1") (pinfunction "IN-_1") (pintype "passive"))
    )
    (net (code "17") (name "/Iout+") (class "Default")
      (node (ref "H10") (pin "1") (pinfunction "1_1") (pintype "passive"))
      (node (ref "U7") (pin "8") (pinfunction "IN+_8") (pintype "passive"))
    )
    (net (code "18") (name "/Iout-") (class "Default")
      (node (ref "H10") (pin "2") (pinfunction "2_2") (pintype "passive"))
      (node (ref "R30") (pin "2") (pinfunction "2_2") (pintype "passive"))
      (node (ref "U7") (pin "1") (pinfunction "IN-_1") (pintype "passive"))
    )
    (net (code "19") (name "/Key1") (class "Default")
      (node (ref "K2") (pin "3") (pinfunction "3_3") (pintype "passive"))
      (node (ref "R19") (pin "1") (pinfunction "1_1") (pintype "passive"))
      (node (ref "U10") (pin "63") (pinfunction "PC6_63") (pintype "passive"))
    )
    (net (code "20") (name "/Key2") (class "Default")
      (node (ref "K3") (pin "3") (pinfunction "3_3") (pintype "passive"))
      (node (ref "R20") (pin "1") (pinfunction "1_1") (pintype "passive"))
      (node (ref "U10") (pin "64") (pinfunction "PC7_64") (pintype "passive"))
    )
    (net (code "21") (name "/Key3") (class "Default")
      (node (ref "K4") (pin "3") (pinfunction "3_3") (pintype "passive"))
      (node (ref "R21") (pin "1") (pinfunction "1_1") (pintype "passive"))
      (node (ref "U10") (pin "65") (pinfunction "PC8_65") (pintype "passive"))
    )
    (net (code "22") (name "/LEDA") (class "Default")
      (node (ref "Screen1") (pin "1") (pinfunction "1_1") (pintype "passive"))
      (node (ref "U10") (pin "59") (pinfunction "PD12_59") (pintype "passive"))
    )
    (net (code "23") (name "/LEDB-") (class "Default")
      (node (ref "LED1") (pin "1") (pinfunction "B-_1") (pintype "passive"))
      (node (ref "U10") (pin "62") (pinfunction "PD15_62") (pintype "passive"))
    )
    (net (code "24") (name "/LEDG-") (class "Default")
      (node (ref "LED1") (pin "5") (pinfunction "G-_5") (pintype "passive"))
      (node (ref "U10") (pin "60") (pinfunction "PD13_60") (pintype "passive"))
    )
    (net (code "25") (name "/LEDR-") (class "Default")
      (node (ref "LED1") (pin "3") (pinfunction "R-_3") (pintype "passive"))
      (node (ref "U10") (pin "61") (pinfunction "PD14_61") (pintype "passive"))
    )
    (net (code "26") (name "/NRST") (class "Default")
      (node (ref "H7") (pin "7") (pinfunction "7_7") (pintype "passive"))
      (node (ref "K1") (pin "3") (pinfunction "3_3") (pintype "passive"))
      (node (ref "R18") (pin "1") (pinfunction "1_1") (pintype "passive"))
      (node (ref "U10") (pin "14") (pinfunction "NRST_14") (pintype "passive"))
    )
    (net (code "27") (name "/OSC_IN") (class "Default")
      (node (ref "C30") (pin "1") (pinfunction "1_1") (pintype "passive"))
      (node (ref "U10") (pin "12") (pinfunction "PH0-OSC_IN_12") (pintype "passive"))
      (node (ref "X1") (pin "3") (pinfunction "OUT_3") (pintype "passive"))
    )
    (net (code "28") (name "/PWMAH") (class "Default")
      (node (ref "H8") (pin "1") (pinfunction "1_1") (pintype "passive"))
      (node (ref "U10") (pin "39") (pinfunction "PE9_39") (pintype "passive"))
    )
    (net (code "29") (name "/PWMAL") (class "Default")
      (node (ref "H8") (pin "2") (pinfunction "2_2") (pintype "passive"))
      (node (ref "U10") (pin "38") (pinfunction "PE8_38") (pintype "passive"))
    )
    (net (code "30") (name "/PWMBH") (class "Default")
      (node (ref "H13") (pin "1") (pinfunction "1_1") (pintype "passive"))
      (node (ref "U10") (pin "41") (pinfunction "PE11_41") (pintype "passive"))
    )
    (net (code "31") (name "/PWMBL") (class "Default")
      (node (ref "H13") (pin "2") (pinfunction "2_2") (pintype "passive"))
      (node (ref "U10") (pin "40") (pinfunction "PE10_40") (pintype "passive"))
    )
    (net (code "32") (name "/RESET") (class "Default")
      (node (ref "Screen1") (pin "3") (pinfunction "3_3") (pintype "passive"))
      (node (ref "U10") (pin "56") (pinfunction "PD9_56") (pintype "passive"))
    )
    (net (code "33") (name "/RS") (class "Default")
      (node (ref "Screen1") (pin "4") (pinfunction "4_4") (pintype "passive"))
      (node (ref "U10") (pin "55") (pinfunction "PD8_55") (pintype "passive"))
    )
    (net (code "34") (name "/SCL") (class "Default")
      (node (ref "Screen1") (pin "6") (pinfunction "6_6") (pintype "passive"))
      (node (ref "U10") (pin "52") (pinfunction "PB13_52") (pintype "passive"))
    )
    (net (code "35") (name "/SDA") (class "Default")
      (node (ref "Screen1") (pin "5") (pinfunction "5_5") (pintype "passive"))
      (node (ref "U10") (pin "54") (pinfunction "PB15_54") (pintype "passive"))
    )
    (net (code "36") (name "/SWCLK") (class "Default")
      (node (ref "R33") (pin "1") (pinfunction "1_1") (pintype "passive"))
      (node (ref "R38") (pin "2") (pinfunction "2_2") (pintype "passive"))
      (node (ref "U10") (pin "76") (pinfunction "PA14_76") (pintype "passive"))
    )
    (net (code "37") (name "/SWDIO") (class "Default")
      (node (ref "R35") (pin "1") (pinfunction "1_1") (pintype "passive"))
      (node (ref "R37") (pin "2") (pinfunction "2_2") (pintype "passive"))
      (node (ref "U10") (pin "72") (pinfunction "PA13_72") (pintype "passive"))
    )
    (net (code "38") (name "/USART1_RX") (class "Default")
      (node (ref "H7") (pin "5") (pinfunction "5_5") (pintype "passive"))
      (node (ref "U10") (pin "69") (pinfunction "PA10_69") (pintype "passive"))
    )
    (net (code "39") (name "/USART1_TX") (class "Default")
      (node (ref "H7") (pin "6") (pinfunction "6_6") (pintype "passive"))
      (node (ref "U10") (pin "68") (pinfunction "PA9_68") (pintype "passive"))
    )
    (net (code "40") (name "/Vin-") (class "Default")
      (node (ref "H9") (pin "3") (pinfunction "3_3") (pintype "passive"))
      (node (ref "R27") (pin "1") (pinfunction "1_1") (pintype "passive"))
    )
    (net (code "41") (name "/Vout-") (class "Default")
      (node (ref "H10") (pin "3") (pinfunction "3_3") (pintype "passive"))
      (node (ref "R28") (pin "2") (pinfunction "2_2") (pintype "passive"))
    )
    (net (code "42") (name "/Vref+") (class "Default")
      (node (ref "C26") (pin "2") (pinfunction "2_2") (pintype "passive"))
      (node (ref "C34") (pin "1") (pinfunction "1_1") (pintype "passive"))
      (node (ref "C35") (pin "2") (pinfunction "2_2") (pintype "passive"))
      (node (ref "C36") (pin "2") (pinfunction "2_2") (pintype "passive"))
      (node (ref "C37") (pin "1") (pinfunction "1_1") (pintype "passive"))
      (node (ref "U10") (pin "20") (pinfunction "VREF+_20") (pintype "passive"))
      (node (ref "U5") (pin "3") (pinfunction "REF2_3") (pintype "passive"))
      (node (ref "U6") (pin "3") (pinfunction "REF2_3") (pintype "passive"))
      (node (ref "U7") (pin "3") (pinfunction "REF2_3") (pintype "passive"))
      (node (ref "U9") (pin "2") (pinfunction "OUT_2") (pintype "passive"))
    )
    (net (code "43") (name "AGND") (class "Default")
      (node (ref "C19") (pin "1") (pinfunction "1_1") (pintype "passive"))
      (node (ref "C20") (pin "1") (pinfunction "1_1") (pintype "passive"))
      (node (ref "C21") (pin "1") (pinfunction "1_1") (pintype "passive"))
      (node (ref "C22") (pin "1") (pinfunction "1_1") (pintype "passive"))
      (node (ref "C23") (pin "1") (pinfunction "1_1") (pintype "passive"))
      (node (ref "C24") (pin "1") (pinfunction "1_1") (pintype "passive"))
      (node (ref "C25") (pin "2") (pinfunction "2_2") (pintype "passive"))
      (node (ref "C26") (pin "1") (pinfunction "1_1") (pintype "passive"))
      (node (ref "C27") (pin "2") (pinfunction "2_2") (pintype "passive"))
      (node (ref "C28") (pin "1") (pinfunction "1_1") (pintype "passive"))
      (node (ref "C29") (pin "1") (pinfunction "1_1") (pintype "passive"))
      (node (ref "C30") (pin "2") (pinfunction "2_2") (pintype "passive"))
      (node (ref "C31") (pin "1") (pinfunction "1_1") (pintype "passive"))
      (node (ref "C32") (pin "1") (pinfunction "1_1") (pintype "passive"))
      (node (ref "C33") (pin "1") (pinfunction "1_1") (pintype "passive"))
      (node (ref "C34") (pin "2") (pinfunction "2_2") (pintype "passive"))
      (node (ref "C35") (pin "1") (pinfunction "1_1") (pintype "passive"))
      (node (ref "C36") (pin "1") (pinfunction "1_1") (pintype "passive"))
      (node (ref "C37") (pin "2") (pinfunction "2_2") (pintype "passive"))
      (node (ref "C38") (pin "1") (pinfunction "1_1") (pintype "passive"))
      (node (ref "C39") (pin "1") (pinfunction "1_1") (pintype "passive"))
      (node (ref "C40") (pin "2") (pinfunction "2_2") (pintype "passive"))
      (node (ref "C41") (pin "2") (pinfunction "2_2") (pintype "passive"))
      (node (ref "C42") (pin "2") (pinfunction "2_2") (pintype "passive"))
      (node (ref "D4") (pin "3") (pinfunction "3_3") (pintype "passive"))
      (node (ref "H11") (pin "2") (pinfunction "2_2") (pintype "passive"))
      (node (ref "H13") (pin "4") (pinfunction "4_4") (pintype "passive"))
      (node (ref "H7") (pin "1") (pinfunction "1_1") (pintype "passive"))
      (node (ref "H8") (pin "4") (pinfunction "4_4") (pintype "passive"))
      (node (ref "K1") (pin "1") (pinfunction "1_1") (pintype "passive"))
      (node (ref "K2") (pin "1") (pinfunction "1_1") (pintype "passive"))
      (node (ref "K3") (pin "1") (pinfunction "1_1") (pintype "passive"))
      (node (ref "K4") (pin "1") (pinfunction "1_1") (pintype "passive"))
      (node (ref "LED") (pin "2") (pinfunction "K_2") (pintype "passive"))
      (node (ref "R31") (pin "1") (pinfunction "1_1") (pintype "passive"))
      (node (ref "R32") (pin "1") (pinfunction "1_1") (pintype "passive"))
      (node (ref "R33") (pin "2") (pinfunction "2_2") (pintype "passive"))
      (node (ref "R41") (pin "1") (pinfunction "1_1") (pintype "passive"))
      (node (ref "Screen1") (pin "2") (pinfunction "2_2") (pintype "passive"))
      (node (ref "U10") (pin "10") (pinfunction "VSS_10") (pintype "passive"))
      (node (ref "U10") (pin "19") (pinfunction "VSSA_19") (pintype "passive"))
      (node (ref "U10") (pin "26") (pinfunction "VSS_26") (pintype "passive"))
      (node (ref "U10") (pin "49") (pinfunction "VSS_49") (pintype "passive"))
      (node (ref "U10") (pin "74") (pinfunction "VSS_74") (pintype "passive"))
      (node (ref "U10") (pin "99") (pinfunction "VSS_99") (pintype "passive"))
      (node (ref "U11") (pin "2") (pinfunction "GND_2") (pintype "passive"))
      (node (ref "U11") (pin "8") (pinfunction "RS_8") (pintype "passive"))
      (node (ref "U4") (pin "1") (pinfunction "GND_1") (pintype "power_in"))
      (node (ref "U5") (pin "2") (pinfunction "GND_2") (pintype "passive"))
      (node (ref "U5") (pin "7") (pinfunction "REF1_7") (pintype "passive"))
      (node (ref "U6") (pin "2") (pinfunction "GND_2") (pintype "passive"))
      (node (ref "U6") (pin "7") (pinfunction "REF1_7") (pintype "passive"))
      (node (ref "U7") (pin "2") (pinfunction "GND_2") (pintype "passive"))
      (node (ref "U7") (pin "7") (pinfunction "REF1_7") (pintype "passive"))
      (node (ref "U8") (pin "4") (pinfunction "VSS_4") (pintype "passive"))
      (node (ref "U9") (pin "3") (pinfunction "GND_3") (pintype "passive"))
      (node (ref "X1") (pin "2") (pinfunction "GND_2") (pintype "passive"))
    )
    (net (code "44") (name "Net-(C38-Pad2)") (class "Default")
      (node (ref "C38") (pin "2") (pinfunction "2_2") (pintype "passive"))
      (node (ref "U10") (pin "73") (pinfunction "VCAP_73") (pintype "passive"))
    )
    (net (code "45") (name "Net-(C40-Pad1)") (class "Default")
      (node (ref "C40") (pin "1") (pinfunction "1_1") (pintype "passive"))
      (node (ref "U10") (pin "48") (pinfunction "VCAP_48") (pintype "passive"))
    )
    (net (code "46") (name "Net-(H7-Pad3)") (class "Default")
      (node (ref "H7") (pin "3") (pinfunction "3_3") (pintype "passive"))
      (node (ref "R37") (pin "1") (pinfunction "1_1") (pintype "passive"))
    )
    (net (code "47") (name "Net-(H7-Pad4)") (class "Default")
      (node (ref "H7") (pin "4") (pinfunction "4_4") (pintype "passive"))
      (node (ref "R38") (pin "1") (pinfunction "1_1") (pintype "passive"))
    )
    (net (code "48") (name "Net-(LED-A)") (class "Default")
      (node (ref "LED") (pin "1") (pinfunction "A_1") (pintype "passive"))
      (node (ref "R36") (pin "2") (pinfunction "2_2") (pintype "passive"))
    )
    (net (code "49") (name "Net-(LED1-B+)") (class "Default")
      (node (ref "LED1") (pin "2") (pinfunction "B+_2") (pintype "passive"))
      (node (ref "R22") (pin "1") (pinfunction "1_1") (pintype "passive"))
    )
    (net (code "50") (name "Net-(LED1-G+)") (class "Default")
      (node (ref "LED1") (pin "6") (pinfunction "G+_6") (pintype "passive"))
      (node (ref "R24") (pin "1") (pinfunction "1_1") (pintype "passive"))
    )
    (net (code "51") (name "Net-(LED1-R+)") (class "Default")
      (node (ref "LED1") (pin "4") (pinfunction "R+_4") (pintype "passive"))
      (node (ref "R23") (pin "1") (pinfunction "1_1") (pintype "passive"))
    )
    (net (code "52") (name "Net-(R34-Pad2)") (class "Default")
      (node (ref "R34") (pin "2") (pinfunction "2_2") (pintype "passive"))
      (node (ref "SW1") (pin "1") (pinfunction "1_1") (pintype "passive"))
    )
    (net (code "53") (name "Net-(U8-INA+)") (class "Default")
      (node (ref "R29") (pin "2") (pinfunction "2_2") (pintype "passive"))
      (node (ref "R31") (pin "2") (pinfunction "2_2") (pintype "passive"))
      (node (ref "U8") (pin "3") (pinfunction "INA+_3") (pintype "passive"))
    )
    (net (code "54") (name "Net-(U8-INA-)") (class "Default")
      (node (ref "R25") (pin "1") (pinfunction "1_1") (pintype "passive"))
      (node (ref "R27") (pin "2") (pinfunction "2_2") (pintype "passive"))
      (node (ref "U8") (pin "2") (pinfunction "INA-_2") (pintype "passive"))
    )
    (net (code "55") (name "Net-(U8-INB+)") (class "Default")
      (node (ref "R30") (pin "1") (pinfunction "1_1") (pintype "passive"))
      (node (ref "R32") (pin "2") (pinfunction "2_2") (pintype "passive"))
      (node (ref "U8") (pin "5") (pinfunction "INB+_5") (pintype "passive"))
    )
    (net (code "56") (name "Net-(U8-INB-)") (class "Default")
      (node (ref "R26") (pin "1") (pinfunction "1_1") (pintype "passive"))
      (node (ref "R28") (pin "1") (pinfunction "1_1") (pintype "passive"))
      (node (ref "U8") (pin "6") (pinfunction "INB-_6") (pintype "passive"))
    )
    (net (code "57") (name "Net-(U10-BOOT0)") (class "Default")
      (node (ref "R41") (pin "2") (pinfunction "2_2") (pintype "passive"))
      (node (ref "U10") (pin "94") (pinfunction "BOOT0_94") (pintype "passive"))
    )
    (net (code "58") (name "Net-(U10-PB8)") (class "Default")
      (node (ref "R40") (pin "2") (pinfunction "2_2") (pintype "passive"))
      (node (ref "U10") (pin "95") (pinfunction "PB8_95") (pintype "passive"))
    )
    (net (code "59") (name "Net-(U10-PB9)") (class "Default")
      (node (ref "R39") (pin "2") (pinfunction "2_2") (pintype "passive"))
      (node (ref "U10") (pin "96") (pinfunction "PB9_96") (pintype "passive"))
    )
    (net (code "60") (name "unconnected-(CN6-Pad3)") (class "Default")
      (node (ref "CN6") (pin "3") (pinfunction "3_3") (pintype "passive+no_connect"))
    )
    (net (code "61") (name "unconnected-(CN6-Pad4)") (class "Default")
      (node (ref "CN6") (pin "4") (pinfunction "4_4") (pintype "passive+no_connect"))
    )
    (net (code "62") (name "unconnected-(CN7-Pad3)") (class "Default")
      (node (ref "CN7") (pin "3") (pinfunction "3_3") (pintype "passive+no_connect"))
    )
    (net (code "63") (name "unconnected-(CN7-Pad4)") (class "Default")
      (node (ref "CN7") (pin "4") (pinfunction "4_4") (pintype "passive+no_connect"))
    )
    (net (code "64") (name "unconnected-(CN8-Pad3)") (class "Default")
      (node (ref "CN8") (pin "3") (pinfunction "3_3") (pintype "passive+no_connect"))
    )
    (net (code "65") (name "unconnected-(CN8-Pad4)") (class "Default")
      (node (ref "CN8") (pin "4") (pinfunction "4_4") (pintype "passive+no_connect"))
    )
    (net (code "66") (name "unconnected-(K1-Pad2)") (class "Default")
      (node (ref "K1") (pin "2") (pinfunction "2_2") (pintype "passive+no_connect"))
    )
    (net (code "67") (name "unconnected-(K1-Pad4)") (class "Default")
      (node (ref "K1") (pin "4") (pinfunction "4_4") (pintype "passive+no_connect"))
    )
    (net (code "68") (name "unconnected-(K2-Pad2)") (class "Default")
      (node (ref "K2") (pin "2") (pinfunction "2_2") (pintype "passive+no_connect"))
    )
    (net (code "69") (name "unconnected-(K2-Pad4)") (class "Default")
      (node (ref "K2") (pin "4") (pinfunction "4_4") (pintype "passive+no_connect"))
    )
    (net (code "70") (name "unconnected-(K3-Pad2)") (class "Default")
      (node (ref "K3") (pin "2") (pinfunction "2_2") (pintype "passive+no_connect"))
    )
    (net (code "71") (name "unconnected-(K3-Pad4)") (class "Default")
      (node (ref "K3") (pin "4") (pinfunction "4_4") (pintype "passive+no_connect"))
    )
    (net (code "72") (name "unconnected-(K4-Pad2)") (class "Default")
      (node (ref "K4") (pin "2") (pinfunction "2_2") (pintype "passive+no_connect"))
    )
    (net (code "73") (name "unconnected-(K4-Pad4)") (class "Default")
      (node (ref "K4") (pin "4") (pinfunction "4_4") (pintype "passive+no_connect"))
    )
    (net (code "74") (name "unconnected-(U5-NC-Pad4)") (class "Default")
      (node (ref "U5") (pin "4") (pinfunction "NC_4") (pintype "passive+no_connect"))
    )
    (net (code "75") (name "unconnected-(U6-NC-Pad4)") (class "Default")
      (node (ref "U6") (pin "4") (pinfunction "NC_4") (pintype "passive+no_connect"))
    )
    (net (code "76") (name "unconnected-(U7-NC-Pad4)") (class "Default")
      (node (ref "U7") (pin "4") (pinfunction "NC_4") (pintype "passive+no_connect"))
    )
    (net (code "77") (name "unconnected-(U10-PA0-Pad22)") (class "Default")
      (node (ref "U10") (pin "22") (pinfunction "PA0_22") (pintype "passive+no_connect"))
    )
    (net (code "78") (name "unconnected-(U10-PA1-Pad23)") (class "Default")
      (node (ref "U10") (pin "23") (pinfunction "PA1_23") (pintype "passive+no_connect"))
    )
    (net (code "79") (name "unconnected-(U10-PA4-Pad28)") (class "Default")
      (node (ref "U10") (pin "28") (pinfunction "PA4_28") (pintype "passive+no_connect"))
    )
    (net (code "80") (name "unconnected-(U10-PA5-Pad29)") (class "Default")
      (node (ref "U10") (pin "29") (pinfunction "PA5_29") (pintype "passive+no_connect"))
    )
    (net (code "81") (name "unconnected-(U10-PA6-Pad30)") (class "Default")
      (node (ref "U10") (pin "30") (pinfunction "PA6_30") (pintype "passive+no_connect"))
    )
    (net (code "82") (name "unconnected-(U10-PA7-Pad31)") (class "Default")
      (node (ref "U10") (pin "31") (pinfunction "PA7_31") (pintype "passive+no_connect"))
    )
    (net (code "83") (name "unconnected-(U10-PA8-Pad67)") (class "Default")
      (node (ref "U10") (pin "67") (pinfunction "PA8_67") (pintype "passive+no_connect"))
    )
    (net (code "84") (name "unconnected-(U10-PA11-Pad70)") (class "Default")
      (node (ref "U10") (pin "70") (pinfunction "PA11_70") (pintype "passive+no_connect"))
    )
    (net (code "85") (name "unconnected-(U10-PA12-Pad71)") (class "Default")
      (node (ref "U10") (pin "71") (pinfunction "PA12_71") (pintype "passive+no_connect"))
    )
    (net (code "86") (name "unconnected-(U10-PA15-Pad77)") (class "Default")
      (node (ref "U10") (pin "77") (pinfunction "PA15_77") (pintype "passive+no_connect"))
    )
    (net (code "87") (name "unconnected-(U10-PB0-Pad34)") (class "Default")
      (node (ref "U10") (pin "34") (pinfunction "PB0_34") (pintype "passive+no_connect"))
    )
    (net (code "88") (name "unconnected-(U10-PB1-Pad35)") (class "Default")
      (node (ref "U10") (pin "35") (pinfunction "PB1_35") (pintype "passive+no_connect"))
    )
    (net (code "89") (name "unconnected-(U10-PB2-Pad36)") (class "Default")
      (node (ref "U10") (pin "36") (pinfunction "PB2_36") (pintype "passive+no_connect"))
    )
    (net (code "90") (name "unconnected-(U10-PB3-Pad89)") (class "Default")
      (node (ref "U10") (pin "89") (pinfunction "PB3_89") (pintype "passive+no_connect"))
    )
    (net (code "91") (name "unconnected-(U10-PB4-Pad90)") (class "Default")
      (node (ref "U10") (pin "90") (pinfunction "PB4_90") (pintype "passive+no_connect"))
    )
    (net (code "92") (name "unconnected-(U10-PB5-Pad91)") (class "Default")
      (node (ref "U10") (pin "91") (pinfunction "PB5_91") (pintype "passive+no_connect"))
    )
    (net (code "93") (name "unconnected-(U10-PB6-Pad92)") (class "Default")
      (node (ref "U10") (pin "92") (pinfunction "PB6_92") (pintype "passive+no_connect"))
    )
    (net (code "94") (name "unconnected-(U10-PB7-Pad93)") (class "Default")
      (node (ref "U10") (pin "93") (pinfunction "PB7_93") (pintype "passive+no_connect"))
    )
    (net (code "95") (name "unconnected-(U10-PB10-Pad46)") (class "Default")
      (node (ref "U10") (pin "46") (pinfunction "PB10_46") (pintype "passive+no_connect"))
    )
    (net (code "96") (name "unconnected-(U10-PB11-Pad47)") (class "Default")
      (node (ref "U10") (pin "47") (pinfunction "PB11_47") (pintype "passive+no_connect"))
    )
    (net (code "97") (name "unconnected-(U10-PB14-Pad53)") (class "Default")
      (node (ref "U10") (pin "53") (pinfunction "PB14_53") (pintype "passive+no_connect"))
    )
    (net (code "98") (name "unconnected-(U10-PC2_C-Pad17)") (class "Default")
      (node (ref "U10") (pin "17") (pinfunction "PC2_C_17") (pintype "passive+no_connect"))
    )
    (net (code "99") (name "unconnected-(U10-PC4-Pad32)") (class "Default")
      (node (ref "U10") (pin "32") (pinfunction "PC4_32") (pintype "passive+no_connect"))
    )
    (net (code "100") (name "unconnected-(U10-PC5-Pad33)") (class "Default")
      (node (ref "U10") (pin "33") (pinfunction "PC5_33") (pintype "passive+no_connect"))
    )
    (net (code "101") (name "unconnected-(U10-PC9-Pad66)") (class "Default")
      (node (ref "U10") (pin "66") (pinfunction "PC9_66") (pintype "passive+no_connect"))
    )
    (net (code "102") (name "unconnected-(U10-PC10-Pad78)") (class "Default")
      (node (ref "U10") (pin "78") (pinfunction "PC10_78") (pintype "passive+no_connect"))
    )
    (net (code "103") (name "unconnected-(U10-PC11-Pad79)") (class "Default")
      (node (ref "U10") (pin "79") (pinfunction "PC11_79") (pintype "passive+no_connect"))
    )
    (net (code "104") (name "unconnected-(U10-PC12-Pad80)") (class "Default")
      (node (ref "U10") (pin "80") (pinfunction "PC12_80") (pintype "passive+no_connect"))
    )
    (net (code "105") (name "unconnected-(U10-PC13-Pad7)") (class "Default")
      (node (ref "U10") (pin "7") (pinfunction "PC13_7") (pintype "passive+no_connect"))
    )
    (net (code "106") (name "unconnected-(U10-PC14-OSC32_IN-Pad8)") (class "Default")
      (node (ref "U10") (pin "8") (pinfunction "PC14-OSC32_IN_8") (pintype "passive+no_connect"))
    )
    (net (code "107") (name "unconnected-(U10-PC15-OSC32_OUT-Pad9)") (class "Default")
      (node (ref "U10") (pin "9") (pinfunction "PC15-OSC32_OUT_9") (pintype "passive+no_connect"))
    )
    (net (code "108") (name "unconnected-(U10-PD0-Pad81)") (class "Default")
      (node (ref "U10") (pin "81") (pinfunction "PD0_81") (pintype "passive+no_connect"))
    )
    (net (code "109") (name "unconnected-(U10-PD1-Pad82)") (class "Default")
      (node (ref "U10") (pin "82") (pinfunction "PD1_82") (pintype "passive+no_connect"))
    )
    (net (code "110") (name "unconnected-(U10-PD2-Pad83)") (class "Default")
      (node (ref "U10") (pin "83") (pinfunction "PD2_83") (pintype "passive+no_connect"))
    )
    (net (code "111") (name "unconnected-(U10-PD3-Pad84)") (class "Default")
      (node (ref "U10") (pin "84") (pinfunction "PD3_84") (pintype "passive+no_connect"))
    )
    (net (code "112") (name "unconnected-(U10-PD4-Pad85)") (class "Default")
      (node (ref "U10") (pin "85") (pinfunction "PD4_85") (pintype "passive+no_connect"))
    )
    (net (code "113") (name "unconnected-(U10-PD5-Pad86)") (class "Default")
      (node (ref "U10") (pin "86") (pinfunction "PD5_86") (pintype "passive+no_connect"))
    )
    (net (code "114") (name "unconnected-(U10-PD6-Pad87)") (class "Default")
      (node (ref "U10") (pin "87") (pinfunction "PD6_87") (pintype "passive+no_connect"))
    )
    (net (code "115") (name "unconnected-(U10-PD7-Pad88)") (class "Default")
      (node (ref "U10") (pin "88") (pinfunction "PD7_88") (pintype "passive+no_connect"))
    )
    (net (code "116") (name "unconnected-(U10-PD10-Pad57)") (class "Default")
      (node (ref "U10") (pin "57") (pinfunction "PD10_57") (pintype "passive+no_connect"))
    )
    (net (code "117") (name "unconnected-(U10-PD11-Pad58)") (class "Default")
      (node (ref "U10") (pin "58") (pinfunction "PD11_58") (pintype "passive+no_connect"))
    )
    (net (code "118") (name "unconnected-(U10-PE0-Pad97)") (class "Default")
      (node (ref "U10") (pin "97") (pinfunction "PE0_97") (pintype "passive+no_connect"))
    )
    (net (code "119") (name "unconnected-(U10-PE1-Pad98)") (class "Default")
      (node (ref "U10") (pin "98") (pinfunction "PE1_98") (pintype "passive+no_connect"))
    )
    (net (code "120") (name "unconnected-(U10-PE2-Pad1)") (class "Default")
      (node (ref "U10") (pin "1") (pinfunction "PE2_1") (pintype "passive+no_connect"))
    )
    (net (code "121") (name "unconnected-(U10-PE3-Pad2)") (class "Default")
      (node (ref "U10") (pin "2") (pinfunction "PE3_2") (pintype "passive+no_connect"))
    )
    (net (code "122") (name "unconnected-(U10-PE4-Pad3)") (class "Default")
      (node (ref "U10") (pin "3") (pinfunction "PE4_3") (pintype "passive+no_connect"))
    )
    (net (code "123") (name "unconnected-(U10-PE5-Pad4)") (class "Default")
      (node (ref "U10") (pin "4") (pinfunction "PE5_4") (pintype "passive+no_connect"))
    )
    (net (code "124") (name "unconnected-(U10-PE6-Pad5)") (class "Default")
      (node (ref "U10") (pin "5") (pinfunction "PE6_5") (pintype "passive+no_connect"))
    )
    (net (code "125") (name "unconnected-(U10-PE7-Pad37)") (class "Default")
      (node (ref "U10") (pin "37") (pinfunction "PE7_37") (pintype "passive+no_connect"))
    )
    (net (code "126") (name "unconnected-(U10-PE12-Pad42)") (class "Default")
      (node (ref "U10") (pin "42") (pinfunction "PE12_42") (pintype "passive+no_connect"))
    )
    (net (code "127") (name "unconnected-(U10-PE13-Pad43)") (class "Default")
      (node (ref "U10") (pin "43") (pinfunction "PE13_43") (pintype "passive+no_connect"))
    )
    (net (code "128") (name "unconnected-(U10-PE14-Pad44)") (class "Default")
      (node (ref "U10") (pin "44") (pinfunction "PE14_44") (pintype "passive+no_connect"))
    )
    (net (code "129") (name "unconnected-(U10-PE15-Pad45)") (class "Default")
      (node (ref "U10") (pin "45") (pinfunction "PE15_45") (pintype "passive+no_connect"))
    )
    (net (code "130") (name "unconnected-(U10-PH1-OSC_OUT-Pad13)") (class "Default")
      (node (ref "U10") (pin "13") (pinfunction "PH1-OSC_OUT_13") (pintype "passive+no_connect"))
    )
    (net (code "131") (name "unconnected-(U11-VREF-Pad5)") (class "Default")
      (node (ref "U11") (pin "5") (pinfunction "VREF_5") (pintype "passive+no_connect"))
    )
    (net (code "132") (name "unconnected-(X1-TRL-Pad1)") (class "Default")
      (node (ref "X1") (pin "1") (pinfunction "TRL_1") (pintype "passive+no_connect"))
    )
  )
)
